# RF_Sensors.net
KiCad netlist of a schematic drawn in Altium Designer
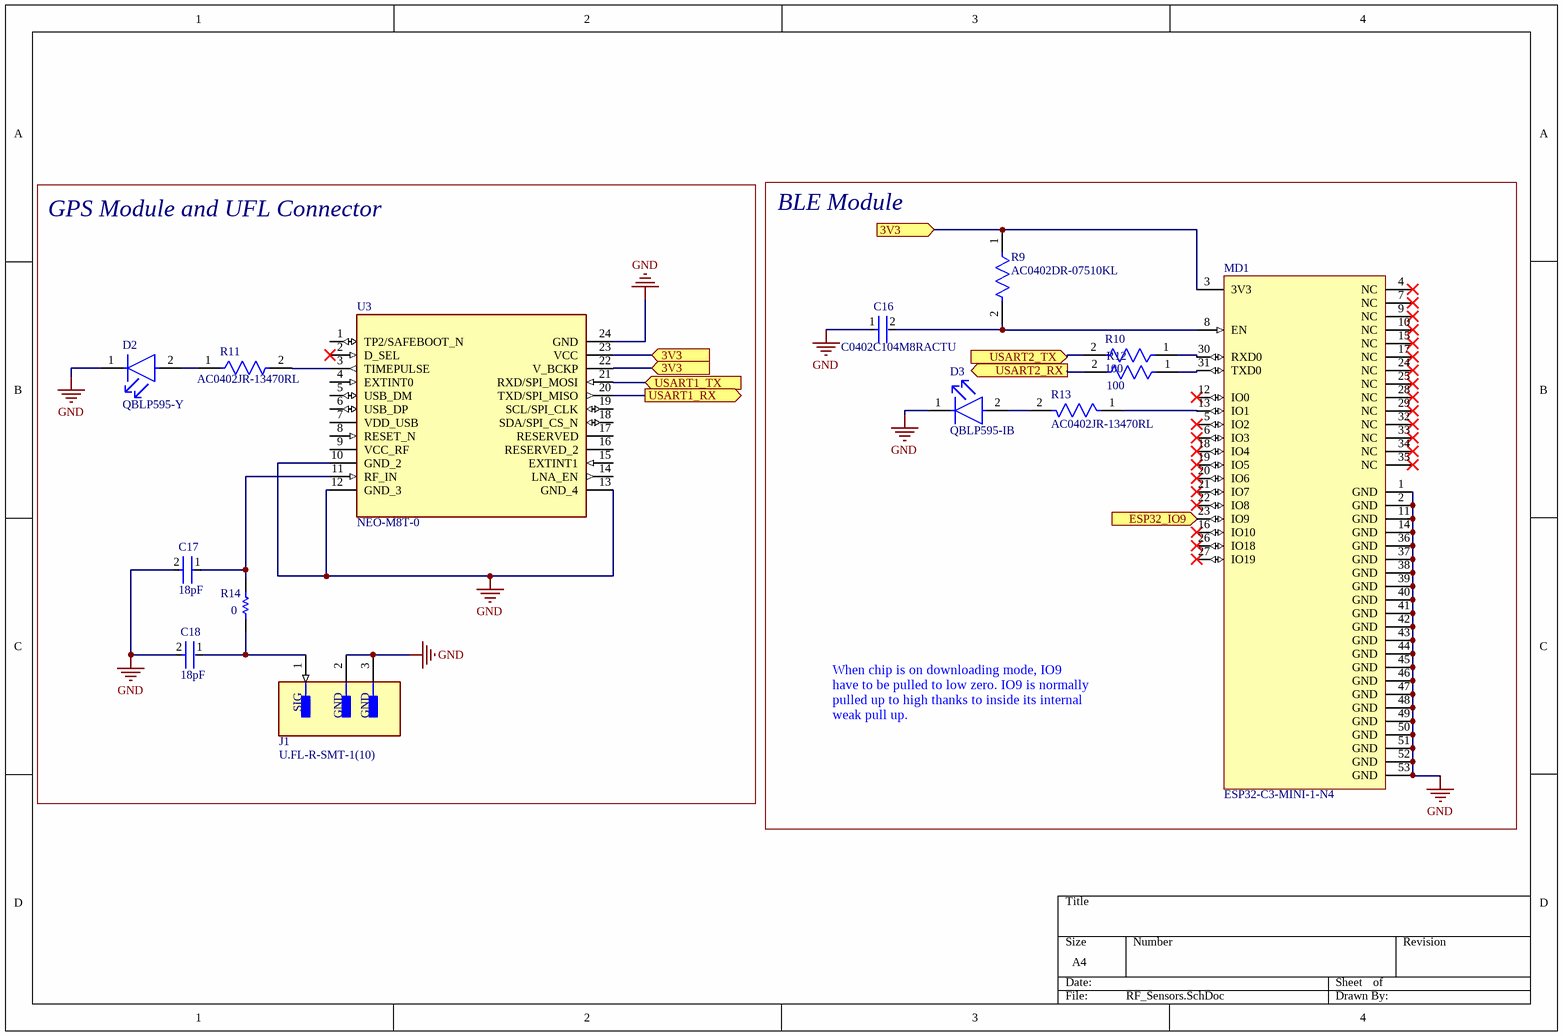
[diagram p0: RF_Sensors.SchDoc]

(export (version "E")
  (design (tool "Eeschema 10.0.6"))
  (components
    (comp (ref "C16")
      (value "C0402C104M8RACTU")
      (footprint "FP-C0402-BB-MFG")
      (description "CAP CER 0.1UF 10V 20% X7R 0402")
      (fields
        (field (name "OCTOPART") "https://octopart.com/c0402c104m8ractu-kemet-9144037")
        (field (name "TOLERANCE") "0.2")
      )
      (libsource (lib "Altium Content Vault") (part "b4654b650e69147ec39a6b967a45e02"))
    )
    (comp (ref "C17")
      (value "18pF")
      (footprint "FP-CBR04C-MFG")
      (description "CAP CER 18PF 100V C0G/NP0 0402")
      (fields
        (field (name "MANUFACTURER PART NUMBER") "CBR04C180F1GAC")
        (field (name "MANUFACTURER") "KEMET")
      )
      (libsource (lib "Altium Content Vault") (part "236180d848d6139a670b325ea6854c9"))
    )
    (comp (ref "C18")
      (value "18pF")
      (footprint "FP-CBR04C-MFG")
      (description "CAP CER 18PF 100V C0G/NP0 0402")
      (fields
        (field (name "MANUFACTURER PART NUMBER") "CBR04C180F1GAC")
        (field (name "MANUFACTURER") "KEMET")
      )
      (libsource (lib "Altium Content Vault") (part "236180d848d6139a670b325ea6854c9"))
    )
    (comp (ref "D2")
      (value "QBLP595-Y")
      (footprint "FP-QBLP595-Y-MFG")
      (description "LED YELLOW CLEAR 0402 SMD")
      (libsource (lib "Altium Content Vault") (part "8706943c75ba83719d021d2fdc84c58"))
    )
    (comp (ref "D3")
      (value "QBLP595-IB")
      (footprint "FP-QBLP595-IB-MFG")
      (description "LED BLUE CLEAR 0402 SMD")
      (libsource (lib "Altium Content Vault") (part "8706943c75ba83719d021d2fdc84c58"))
    )
    (comp (ref "J1")
      (value "U.FL-R-SMT-1(10)")
      (footprint "FP-U_FL-R-SMT-1_10-MFG")
      (description "CONN U.FL RCPT STR 50 OHM SMD")
      (libsource (lib "Altium Content Vault") (part "7158abf7d987fa84906f6fb0d115710"))
    )
    (comp (ref "MD1")
      (value "ESP32-C3-MINI-1-N4")
      (footprint "FP-ESP32-C3-MINI-1-N4-MFG")
      (description "Multiprotocol Modules SMD module, ESP32-C3FN4, PCB antenna, -40 C +85 C")
      (libsource (lib "Altium Content Vault") (part "ESP32-C3-MINI-1-N4"))
    )
    (comp (ref "R9")
      (value "AC0402DR-07510KL")
      (footprint "FP-AC0402-IPC_C")
      (description "RES 510kΩ ±0.5% 0.063W 0402")
      (libsource (lib "Altium Content Vault") (part "1029c3af85768c4190bb7ad29bc67b5"))
    )
    (comp (ref "R10")
      (value "100")
      (footprint "FP-AC0402-MFG")
      (description "RES 100Ω ±1% 0.063W 0402")
      (fields (field (name "TOLERANCE") "1%"))
      (libsource (lib "Altium Content Vault") (part "1029c3af85768c4190bb7ad29bc67b5"))
    )
    (comp (ref "R11")
      (value "AC0402JR-13470RL")
      (footprint "FP-AC0402-MFG")
      (description "RES 470Ω ±5% 0.063W 0402")
      (libsource (lib "Altium Content Vault") (part "1029c3af85768c4190bb7ad29bc67b5"))
    )
    (comp (ref "R12")
      (value "100")
      (footprint "FP-AC0402-MFG")
      (description "RES 100Ω ±1% 0.063W 0402")
      (fields (field (name "TOLERANCE") "1%"))
      (libsource (lib "Altium Content Vault") (part "1029c3af85768c4190bb7ad29bc67b5"))
    )
    (comp (ref "R13")
      (value "AC0402JR-13470RL")
      (footprint "FP-AC0402-MFG")
      (description "RES 470Ω ±5% 0.063W 0402")
      (libsource (lib "Altium Content Vault") (part "1029c3af85768c4190bb7ad29bc67b5"))
    )
    (comp (ref "R14")
      (value "0")
      (footprint "RESC1005X40X25NL05T10")
      (fields (field (name "PART NUMBER") "RC0402JR-100RL") (field (name "MANUFACTURER") "Yageo"))
      (libsource (lib "Altium Content Vault") (part "RES"))
    )
    (comp (ref "U3")
      (value "NEO-M8T-0")
      (footprint "NEO-M8T_UBL")
      (description "series RF Receiver BeiDou, Galileo, GLONASS, GNSS, GPS - -167dBm - - -")
      (fields (field (name "MF") "U-Blox"))
      (libsource (lib "NEO-M8T-0") (part "NEO-M8T-0"))
    )
  )
  (nets
    (net (code "1") (name "/3V3") (class "Default")
      (node (ref "MD1") (pin "3") (pinfunction "3V3_3") (pintype "power_in"))
      (node (ref "R9") (pin "1") (pinfunction "1_1") (pintype "passive"))
      (node (ref "U3") (pin "22") (pinfunction "V_BCKP_22") (pintype "power_in"))
      (node (ref "U3") (pin "23") (pinfunction "VCC_23") (pintype "power_in"))
    )
    (net (code "2") (name "/ESP32_IO9") (class "Default")
      (node (ref "MD1") (pin "23") (pinfunction "IO9_23") (pintype "bidirectional"))
    )
    (net (code "3") (name "/USART1_RX") (class "Default")
      (node (ref "U3") (pin "20") (pinfunction "TXD/SPI_MISO_20") (pintype "output"))
    )
    (net (code "4") (name "/USART1_TX") (class "Default")
      (node (ref "U3") (pin "21") (pinfunction "RXD/SPI_MOSI_21") (pintype "input"))
    )
    (net (code "5") (name "/USART2_RX") (class "Default")
      (node (ref "R12") (pin "2") (pinfunction "2_2") (pintype "passive"))
    )
    (net (code "6") (name "/USART2_TX") (class "Default")
      (node (ref "R10") (pin "2") (pinfunction "2_2") (pintype "passive"))
    )
    (net (code "7") (name "GND") (class "Default")
      (node (ref "C16") (pin "1") (pinfunction "1_1") (pintype "passive"))
      (node (ref "C17") (pin "2") (pinfunction "2_2") (pintype "passive"))
      (node (ref "C18") (pin "2") (pinfunction "2_2") (pintype "passive"))
      (node (ref "D2") (pin "1") (pinfunction "C_1") (pintype "passive"))
      (node (ref "D3") (pin "1") (pinfunction "C_1") (pintype "passive"))
      (node (ref "J1") (pin "2") (pinfunction "GND_2") (pintype "power_in"))
      (node (ref "J1") (pin "3") (pinfunction "GND_3") (pintype "power_in"))
      (node (ref "MD1") (pin "1") (pinfunction "GND_1") (pintype "power_in"))
      (node (ref "MD1") (pin "11") (pinfunction "GND_11") (pintype "power_in"))
      (node (ref "MD1") (pin "14") (pinfunction "GND_14") (pintype "power_in"))
      (node (ref "MD1") (pin "2") (pinfunction "GND_2") (pintype "power_in"))
      (node (ref "MD1") (pin "36") (pinfunction "GND_36") (pintype "power_in"))
      (node (ref "MD1") (pin "37") (pinfunction "GND_37") (pintype "power_in"))
      (node (ref "MD1") (pin "38") (pinfunction "GND_38") (pintype "power_in"))
      (node (ref "MD1") (pin "39") (pinfunction "GND_39") (pintype "power_in"))
      (node (ref "MD1") (pin "40") (pinfunction "GND_40") (pintype "power_in"))
      (node (ref "MD1") (pin "41") (pinfunction "GND_41") (pintype "power_in"))
      (node (ref "MD1") (pin "42") (pinfunction "GND_42") (pintype "power_in"))
      (node (ref "MD1") (pin "43") (pinfunction "GND_43") (pintype "power_in"))
      (node (ref "MD1") (pin "44") (pinfunction "GND_44") (pintype "power_in"))
      (node (ref "MD1") (pin "45") (pinfunction "GND_45") (pintype "power_in"))
      (node (ref "MD1") (pin "46") (pinfunction "GND_46") (pintype "power_in"))
      (node (ref "MD1") (pin "47") (pinfunction "GND_47") (pintype "power_in"))
      (node (ref "MD1") (pin "48") (pinfunction "GND_48") (pintype "power_in"))
      (node (ref "MD1") (pin "49") (pinfunction "GND_49") (pintype "power_in"))
      (node (ref "MD1") (pin "50") (pinfunction "GND_50") (pintype "power_in"))
      (node (ref "MD1") (pin "51") (pinfunction "GND_51") (pintype "power_in"))
      (node (ref "MD1") (pin "52") (pinfunction "GND_52") (pintype "power_in"))
      (node (ref "MD1") (pin "53") (pinfunction "GND_53") (pintype "power_in"))
      (node (ref "U3") (pin "10") (pinfunction "GND_2_10") (pintype "passive"))
      (node (ref "U3") (pin "12") (pinfunction "GND_3_12") (pintype "passive"))
      (node (ref "U3") (pin "13") (pinfunction "GND_4_13") (pintype "passive"))
      (node (ref "U3") (pin "24") (pinfunction "GND_24") (pintype "passive"))
    )
    (net (code "8") (name "Net-(D2-A)") (class "Default")
      (node (ref "D2") (pin "2") (pinfunction "A_2") (pintype "passive"))
      (node (ref "R11") (pin "1") (pinfunction "1_1") (pintype "passive"))
    )
    (net (code "9") (name "Net-(D3-A)") (class "Default")
      (node (ref "D3") (pin "2") (pinfunction "A_2") (pintype "passive"))
      (node (ref "R13") (pin "2") (pinfunction "2_2") (pintype "passive"))
    )
    (net (code "10") (name "Net-(J1-SIG)") (class "Default")
      (node (ref "C18") (pin "1") (pinfunction "1_1") (pintype "passive"))
      (node (ref "J1") (pin "1") (pinfunction "SIG_1") (pintype "input"))
      (node (ref "R14") (pin "2") (pinfunction "2_2") (pintype "passive"))
    )
    (net (code "11") (name "Net-(MD1-EN)") (class "Default")
      (node (ref "C16") (pin "2") (pinfunction "2_2") (pintype "passive"))
      (node (ref "MD1") (pin "8") (pinfunction "EN_8") (pintype "input"))
      (node (ref "R9") (pin "2") (pinfunction "2_2") (pintype "passive"))
    )
    (net (code "12") (name "Net-(MD1-IO1)") (class "Default")
      (node (ref "MD1") (pin "13") (pinfunction "IO1_13") (pintype "bidirectional"))
      (node (ref "R13") (pin "1") (pinfunction "1_1") (pintype "passive"))
    )
    (net (code "13") (name "Net-(MD1-RXD0)") (class "Default")
      (node (ref "MD1") (pin "30") (pinfunction "RXD0_30") (pintype "bidirectional"))
      (node (ref "R10") (pin "1") (pinfunction "1_1") (pintype "passive"))
    )
    (net (code "14") (name "Net-(MD1-TXD0)") (class "Default")
      (node (ref "MD1") (pin "31") (pinfunction "TXD0_31") (pintype "bidirectional"))
      (node (ref "R12") (pin "1") (pinfunction "1_1") (pintype "passive"))
    )
    (net (code "15") (name "Net-(U3-RF_IN)") (class "Default")
      (node (ref "C17") (pin "1") (pinfunction "1_1") (pintype "passive"))
      (node (ref "R14") (pin "1") (pinfunction "1_1") (pintype "passive"))
      (node (ref "U3") (pin "11") (pinfunction "RF_IN_11") (pintype "input"))
    )
    (net (code "16") (name "Net-(U3-TIMEPULSE)") (class "Default")
      (node (ref "R11") (pin "2") (pinfunction "2_2") (pintype "passive"))
      (node (ref "U3") (pin "3") (pinfunction "TIMEPULSE_3") (pintype "output"))
    )
    (net (code "17") (name "unconnected-(MD1-IO0-Pad12)") (class "Default")
      (node (ref "MD1") (pin "12") (pinfunction "IO0_12") (pintype "bidirectional+no_connect"))
    )
    (net (code "18") (name "unconnected-(MD1-IO2-Pad5)") (class "Default")
      (node (ref "MD1") (pin "5") (pinfunction "IO2_5") (pintype "bidirectional+no_connect"))
    )
    (net (code "19") (name "unconnected-(MD1-IO3-Pad6)") (class "Default")
      (node (ref "MD1") (pin "6") (pinfunction "IO3_6") (pintype "bidirectional+no_connect"))
    )
    (net (code "20") (name "unconnected-(MD1-IO4-Pad18)") (class "Default")
      (node (ref "MD1") (pin "18") (pinfunction "IO4_18") (pintype "bidirectional+no_connect"))
    )
    (net (code "21") (name "unconnected-(MD1-IO5-Pad19)") (class "Default")
      (node (ref "MD1") (pin "19") (pinfunction "IO5_19") (pintype "bidirectional+no_connect"))
    )
    (net (code "22") (name "unconnected-(MD1-IO6-Pad20)") (class "Default")
      (node (ref "MD1") (pin "20") (pinfunction "IO6_20") (pintype "bidirectional+no_connect"))
    )
    (net (code "23") (name "unconnected-(MD1-IO7-Pad21)") (class "Default")
      (node (ref "MD1") (pin "21") (pinfunction "IO7_21") (pintype "bidirectional+no_connect"))
    )
    (net (code "24") (name "unconnected-(MD1-IO8-Pad22)") (class "Default")
      (node (ref "MD1") (pin "22") (pinfunction "IO8_22") (pintype "bidirectional+no_connect"))
    )
    (net (code "25") (name "unconnected-(MD1-IO10-Pad16)") (class "Default")
      (node (ref "MD1") (pin "16") (pinfunction "IO10_16") (pintype "bidirectional+no_connect"))
    )
    (net (code "26") (name "unconnected-(MD1-IO18-Pad26)") (class "Default")
      (node (ref "MD1") (pin "26") (pinfunction "IO18_26") (pintype "bidirectional+no_connect"))
    )
    (net (code "27") (name "unconnected-(MD1-IO19-Pad27)") (class "Default")
      (node (ref "MD1") (pin "27") (pinfunction "IO19_27") (pintype "bidirectional+no_connect"))
    )
    (net (code "28") (name "unconnected-(MD1-NC-Pad4)") (class "Default")
      (node (ref "MD1") (pin "4") (pinfunction "NC_4") (pintype "passive+no_connect"))
    )
    (net (code "29") (name "unconnected-(MD1-NC-Pad7)") (class "Default")
      (node (ref "MD1") (pin "7") (pinfunction "NC_7") (pintype "passive+no_connect"))
    )
    (net (code "30") (name "unconnected-(MD1-NC-Pad9)") (class "Default")
      (node (ref "MD1") (pin "9") (pinfunction "NC_9") (pintype "passive+no_connect"))
    )
    (net (code "31") (name "unconnected-(MD1-NC-Pad10)") (class "Default")
      (node (ref "MD1") (pin "10") (pinfunction "NC_10") (pintype "passive+no_connect"))
    )
    (net (code "32") (name "unconnected-(MD1-NC-Pad15)") (class "Default")
      (node (ref "MD1") (pin "15") (pinfunction "NC_15") (pintype "passive+no_connect"))
    )
    (net (code "33") (name "unconnected-(MD1-NC-Pad17)") (class "Default")
      (node (ref "MD1") (pin "17") (pinfunction "NC_17") (pintype "passive+no_connect"))
    )
    (net (code "34") (name "unconnected-(MD1-NC-Pad24)") (class "Default")
      (node (ref "MD1") (pin "24") (pinfunction "NC_24") (pintype "passive+no_connect"))
    )
    (net (code "35") (name "unconnected-(MD1-NC-Pad25)") (class "Default")
      (node (ref "MD1") (pin "25") (pinfunction "NC_25") (pintype "passive+no_connect"))
    )
    (net (code "36") (name "unconnected-(MD1-NC-Pad28)") (class "Default")
      (node (ref "MD1") (pin "28") (pinfunction "NC_28") (pintype "passive+no_connect"))
    )
    (net (code "37") (name "unconnected-(MD1-NC-Pad29)") (class "Default")
      (node (ref "MD1") (pin "29") (pinfunction "NC_29") (pintype "passive+no_connect"))
    )
    (net (code "38") (name "unconnected-(MD1-NC-Pad32)") (class "Default")
      (node (ref "MD1") (pin "32") (pinfunction "NC_32") (pintype "passive+no_connect"))
    )
    (net (code "39") (name "unconnected-(MD1-NC-Pad33)") (class "Default")
      (node (ref "MD1") (pin "33") (pinfunction "NC_33") (pintype "passive+no_connect"))
    )
    (net (code "40") (name "unconnected-(MD1-NC-Pad34)") (class "Default")
      (node (ref "MD1") (pin "34") (pinfunction "NC_34") (pintype "passive+no_connect"))
    )
    (net (code "41") (name "unconnected-(MD1-NC-Pad35)") (class "Default")
      (node (ref "MD1") (pin "35") (pinfunction "NC_35") (pintype "passive+no_connect"))
    )
    (net (code "42") (name "unconnected-(U3-D_SEL-Pad2)") (class "Default")
      (node (ref "U3") (pin "2") (pinfunction "D_SEL_2") (pintype "input+no_connect"))
    )
    (net (code "43") (name "unconnected-(U3-EXTINT0-Pad4)") (class "Default")
      (node (ref "U3") (pin "4") (pinfunction "EXTINT0_4") (pintype "input"))
    )
    (net (code "44") (name "unconnected-(U3-EXTINT1-Pad15)") (class "Default")
      (node (ref "U3") (pin "15") (pinfunction "EXTINT1_15") (pintype "input"))
    )
    (net (code "45") (name "unconnected-(U3-LNA_EN-Pad14)") (class "Default")
      (node (ref "U3") (pin "14") (pinfunction "LNA_EN_14") (pintype "output"))
    )
    (net (code "46") (name "unconnected-(U3-RESERVED-Pad17)") (class "Default")
      (node (ref "U3") (pin "17") (pinfunction "RESERVED_17") (pintype "passive"))
    )
    (net (code "47") (name "unconnected-(U3-RESERVED_2-Pad16)") (class "Default")
      (node (ref "U3") (pin "16") (pinfunction "RESERVED_2_16") (pintype "passive"))
    )
    (net (code "48") (name "unconnected-(U3-RESET_N-Pad8)") (class "Default")
      (node (ref "U3") (pin "8") (pinfunction "RESET_N_8") (pintype "input"))
    )
    (net (code "49") (name "unconnected-(U3-SCL{slash}SPI_CLK-Pad19)") (class "Default")
      (node (ref "U3") (pin "19") (pinfunction "SCL/SPI_CLK_19") (pintype "bidirectional"))
    )
    (net (code "50") (name "unconnected-(U3-SDA{slash}SPI_CS_N-Pad18)") (class "Default")
      (node (ref "U3") (pin "18") (pinfunction "SDA/SPI_CS_N_18") (pintype "bidirectional"))
    )
    (net (code "51") (name "unconnected-(U3-TP2{slash}SAFEBOOT_N-Pad1)") (class "Default")
      (node (ref "U3") (pin "1") (pinfunction "TP2/SAFEBOOT_N_1") (pintype "bidirectional"))
    )
    (net (code "52") (name "unconnected-(U3-USB_DM-Pad5)") (class "Default")
      (node (ref "U3") (pin "5") (pinfunction "USB_DM_5") (pintype "bidirectional"))
    )
    (net (code "53") (name "unconnected-(U3-USB_DP-Pad6)") (class "Default")
      (node (ref "U3") (pin "6") (pinfunction "USB_DP_6") (pintype "bidirectional"))
    )
    (net (code "54") (name "unconnected-(U3-VCC_RF-Pad9)") (class "Default")
      (node (ref "U3") (pin "9") (pinfunction "VCC_RF_9") (pintype "power_in"))
    )
    (net (code "55") (name "unconnected-(U3-VDD_USB-Pad7)") (class "Default")
      (node (ref "U3") (pin "7") (pinfunction "VDD_USB_7") (pintype "power_in"))
    )
  )
)
